# untitled.net
KiCad netlist of a schematic drawn in EAGLE
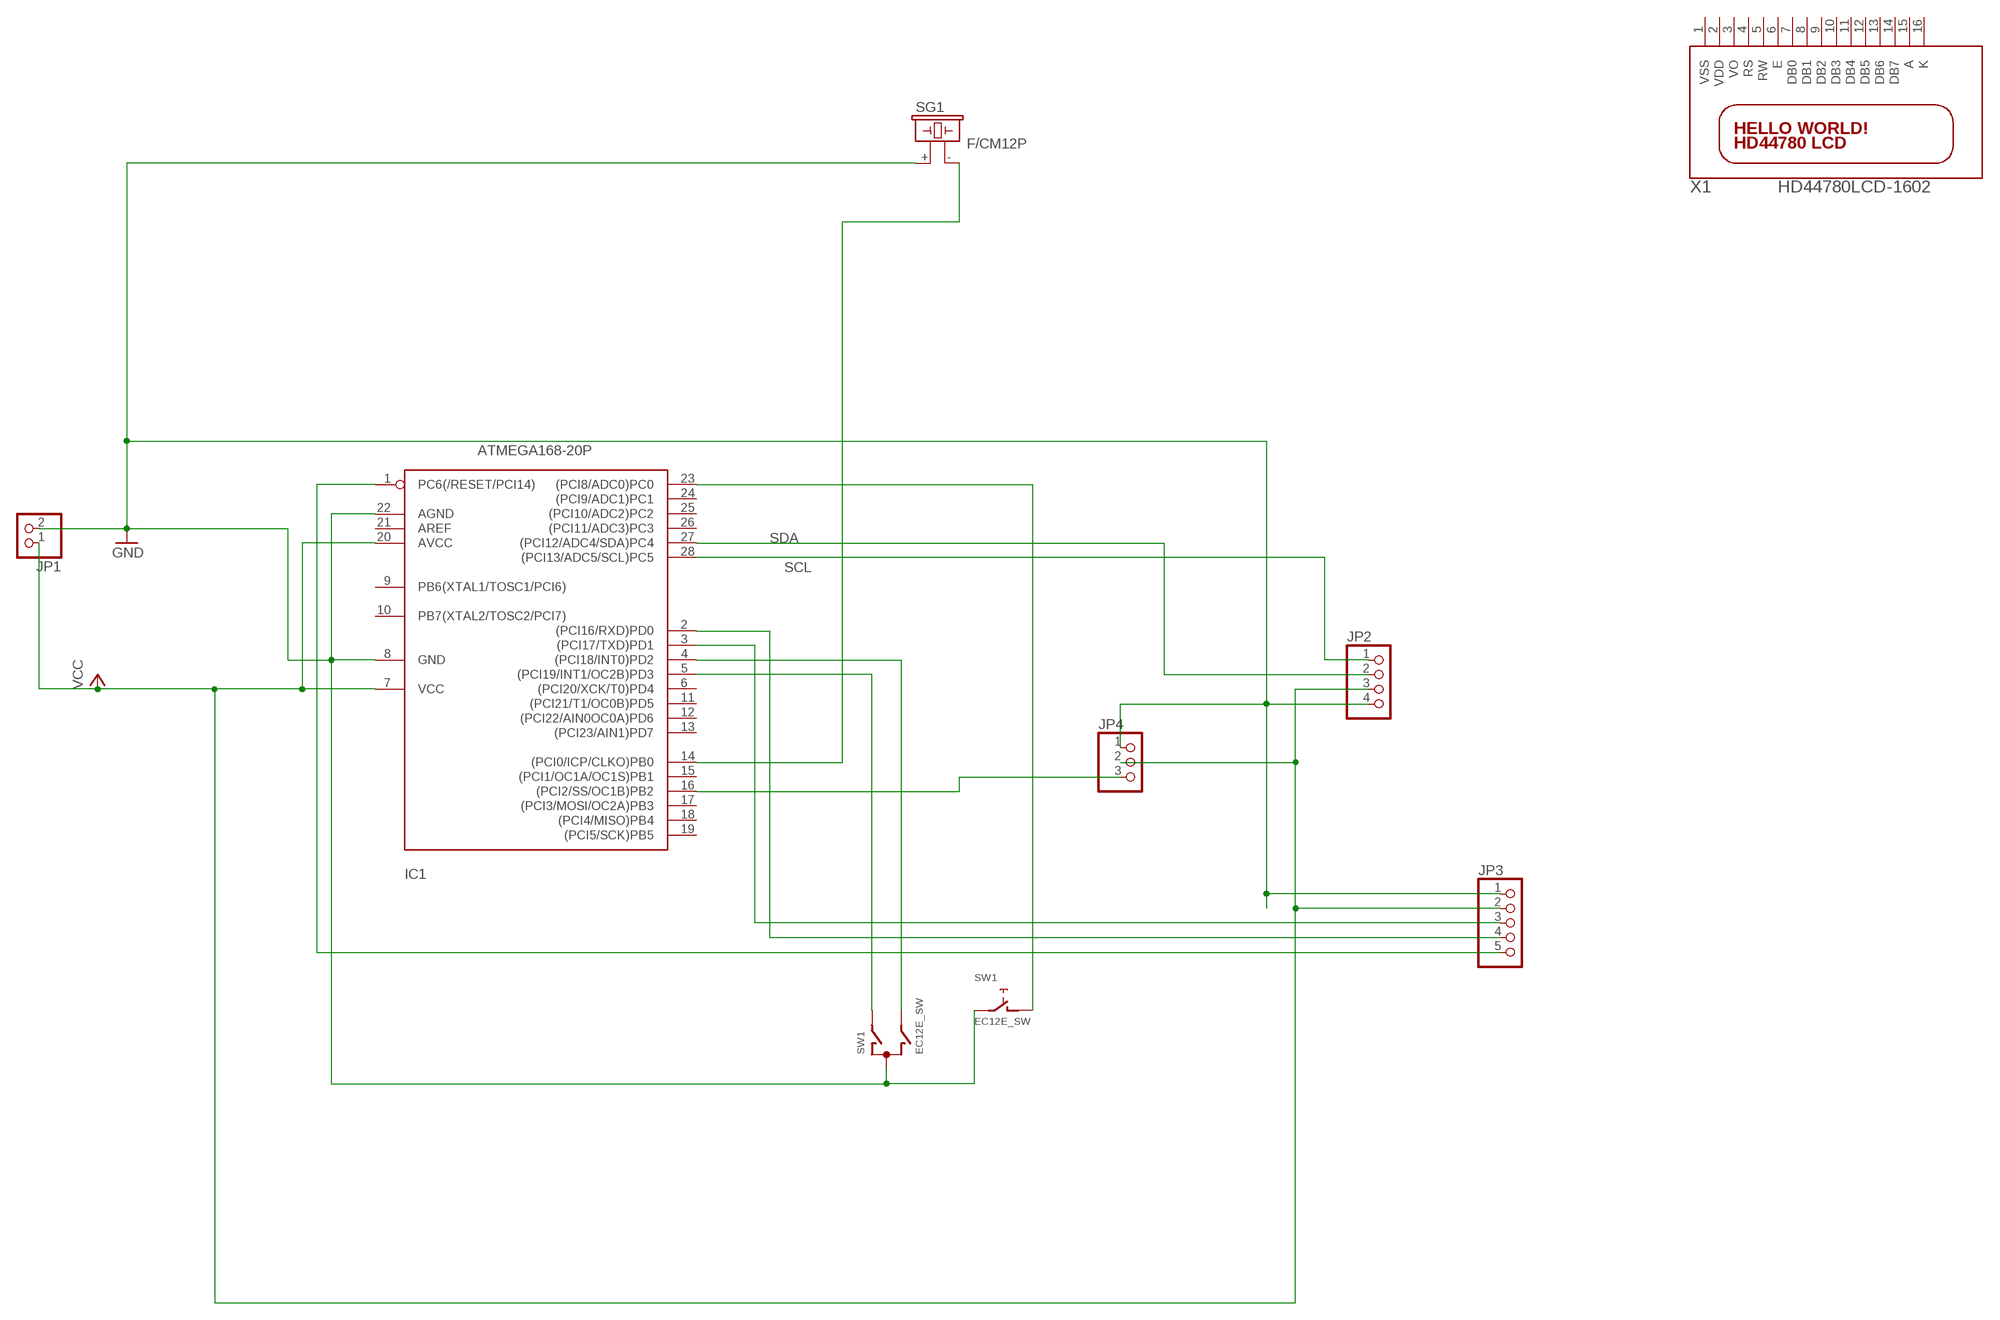
[diagram p0: schematic, sheet 1]

(export (version "E")
  (design (tool "Eeschema 10.0.6"))
  (components
    (comp (ref "IC1")
      (value "ATMEGA168-20P")
      (footprint "eagle-import:DIL28-3")
      (libsource (lib "eagle-import") (part "ATMEGA168P-20"))
    )
    (comp (ref "JP1")
      (value "PINHD-1X2")
      (footprint "eagle-import:1X02")
      (libsource (lib "eagle-import") (part "PINHD-1X2"))
    )
    (comp (ref "JP2")
      (value "PINHD-1X4")
      (footprint "eagle-import:1X04")
      (libsource (lib "eagle-import") (part "PINHD-1X4"))
    )
    (comp (ref "JP3")
      (value "PINHD-1X5")
      (footprint "eagle-import:1X05")
      (libsource (lib "eagle-import") (part "PINHD-1X5"))
    )
    (comp (ref "JP4")
      (value "PINHD-1X3")
      (footprint "eagle-import:1X03")
      (libsource (lib "eagle-import") (part "PINHD-1X3"))
    )
    (comp (ref "SG1")
      (value "F/CM12P")
      (footprint "eagle-import:F_CM12P")
      (libsource (lib "eagle-import") (part "F/CM12P"))
    )
    (comp (ref "SW1")
      (value "EC12E_SW")
      (footprint "eagle-import:ALPS_EC12E_SW")
      (fields (field (name "MPN") "EC12E2424407"))
      (libsource (lib "eagle-import") (part "EC12E_SW"))
    )
    (comp (ref "X1")
      (value "HD44780LCD-1602")
      (footprint "eagle-import:LCD1602")
      (libsource (lib "eagle-import") (part "HD44780LCD-1602"))
    )
  )
  (nets
    (net (code "1") (name "/SCL") (class "Default")
      (node (ref "IC1") (pin "28") (pinfunction "(PCI13/ADC5/SCL)PC5_28") (pintype "bidirectional"))
      (node (ref "JP2") (pin "1") (pinfunction "1_1") (pintype "passive"))
    )
    (net (code "2") (name "/SDA") (class "Default")
      (node (ref "IC1") (pin "27") (pinfunction "(PCI12/ADC4/SDA)PC4_27") (pintype "bidirectional"))
      (node (ref "JP2") (pin "2") (pinfunction "2_2") (pintype "passive"))
    )
    (net (code "3") (name "/VDD") (class "Default")
      (node (ref "X1") (pin "2") (pinfunction "VDD_2") (pintype "power_in"))
    )
    (net (code "4") (name "/VSS") (class "Default")
      (node (ref "X1") (pin "1") (pinfunction "VSS_1") (pintype "power_in"))
    )
    (net (code "5") (name "GND") (class "Default")
      (node (ref "IC1") (pin "22") (pinfunction "AGND_22") (pintype "bidirectional"))
      (node (ref "IC1") (pin "8") (pinfunction "GND_8") (pintype "bidirectional"))
      (node (ref "JP1") (pin "2") (pinfunction "2_2") (pintype "passive"))
      (node (ref "JP2") (pin "4") (pinfunction "4_4") (pintype "passive"))
      (node (ref "JP3") (pin "1") (pinfunction "1_1") (pintype "passive"))
      (node (ref "JP4") (pin "1") (pinfunction "1_1") (pintype "passive"))
      (node (ref "SG1") (pin "+") (pinfunction "1_+") (pintype "passive"))
      (node (ref "SW1") (pin "C") (pinfunction "C_C") (pintype "passive"))
      (node (ref "SW1") (pin "E") (pinfunction "2_E") (pintype "passive"))
    )
    (net (code "6") (name "Net-(IC1-(PCI0{slash}ICP{slash}CLKO)PB0)") (class "Default")
      (node (ref "IC1") (pin "14") (pinfunction "(PCI0/ICP/CLKO)PB0_14") (pintype "bidirectional"))
      (node (ref "SG1") (pin "-") (pinfunction "2_-") (pintype "passive"))
    )
    (net (code "7") (name "Net-(IC1-(PCI2{slash}SS{slash}OC1B)PB2)") (class "Default")
      (node (ref "IC1") (pin "16") (pinfunction "(PCI2/SS/OC1B)PB2_16") (pintype "bidirectional"))
      (node (ref "JP4") (pin "3") (pinfunction "3_3") (pintype "passive"))
    )
    (net (code "8") (name "Net-(IC1-(PCI8{slash}ADC0)PC0)") (class "Default")
      (node (ref "IC1") (pin "23") (pinfunction "(PCI8/ADC0)PC0_23") (pintype "bidirectional"))
      (node (ref "SW1") (pin "D") (pinfunction "1_D") (pintype "passive"))
    )
    (net (code "9") (name "Net-(IC1-(PCI16{slash}RXD)PD0)") (class "Default")
      (node (ref "IC1") (pin "2") (pinfunction "(PCI16/RXD)PD0_2") (pintype "bidirectional"))
      (node (ref "JP3") (pin "4") (pinfunction "4_4") (pintype "passive"))
    )
    (net (code "10") (name "Net-(IC1-(PCI17{slash}TXD)PD1)") (class "Default")
      (node (ref "IC1") (pin "3") (pinfunction "(PCI17/TXD)PD1_3") (pintype "bidirectional"))
      (node (ref "JP3") (pin "3") (pinfunction "3_3") (pintype "passive"))
    )
    (net (code "11") (name "Net-(IC1-(PCI18{slash}INT0)PD2)") (class "Default")
      (node (ref "IC1") (pin "4") (pinfunction "(PCI18/INT0)PD2_4") (pintype "bidirectional"))
      (node (ref "SW1") (pin "B") (pinfunction "B_B") (pintype "passive"))
    )
    (net (code "12") (name "Net-(IC1-(PCI19{slash}INT1{slash}OC2B)PD3)") (class "Default")
      (node (ref "IC1") (pin "5") (pinfunction "(PCI19/INT1/OC2B)PD3_5") (pintype "bidirectional"))
      (node (ref "SW1") (pin "A") (pinfunction "A_A") (pintype "passive"))
    )
    (net (code "13") (name "Net-(IC1-PC6({slash}RESET{slash}PCI14))") (class "Default")
      (node (ref "IC1") (pin "1") (pinfunction "PC6(/RESET/PCI14)_1") (pintype "bidirectional"))
      (node (ref "JP3") (pin "5") (pinfunction "5_5") (pintype "passive"))
    )
    (net (code "14") (name "VCC") (class "Default")
      (node (ref "IC1") (pin "20") (pinfunction "AVCC_20") (pintype "bidirectional"))
      (node (ref "IC1") (pin "7") (pinfunction "VCC_7") (pintype "bidirectional"))
      (node (ref "JP1") (pin "1") (pinfunction "1_1") (pintype "passive"))
      (node (ref "JP2") (pin "3") (pinfunction "3_3") (pintype "passive"))
      (node (ref "JP3") (pin "2") (pinfunction "2_2") (pintype "passive"))
      (node (ref "JP4") (pin "2") (pinfunction "2_2") (pintype "passive"))
    )
    (net (code "15") (name "unconnected-(IC1-(PCI1{slash}OC1A{slash}OC1S)PB1-Pad15)") (class "Default")
      (node (ref "IC1") (pin "15") (pinfunction "(PCI1/OC1A/OC1S)PB1_15") (pintype "bidirectional"))
    )
    (net (code "16") (name "unconnected-(IC1-(PCI3{slash}MOSI{slash}OC2A)PB3-Pad17)") (class "Default")
      (node (ref "IC1") (pin "17") (pinfunction "(PCI3/MOSI/OC2A)PB3_17") (pintype "bidirectional"))
    )
    (net (code "17") (name "unconnected-(IC1-(PCI4{slash}MISO)PB4-Pad18)") (class "Default")
      (node (ref "IC1") (pin "18") (pinfunction "(PCI4/MISO)PB4_18") (pintype "bidirectional"))
    )
    (net (code "18") (name "unconnected-(IC1-(PCI5{slash}SCK)PB5-Pad19)") (class "Default")
      (node (ref "IC1") (pin "19") (pinfunction "(PCI5/SCK)PB5_19") (pintype "bidirectional"))
    )
    (net (code "19") (name "unconnected-(IC1-(PCI9{slash}ADC1)PC1-Pad24)") (class "Default")
      (node (ref "IC1") (pin "24") (pinfunction "(PCI9/ADC1)PC1_24") (pintype "bidirectional"))
    )
    (net (code "20") (name "unconnected-(IC1-(PCI10{slash}ADC2)PC2-Pad25)") (class "Default")
      (node (ref "IC1") (pin "25") (pinfunction "(PCI10/ADC2)PC2_25") (pintype "bidirectional"))
    )
    (net (code "21") (name "unconnected-(IC1-(PCI11{slash}ADC3)PC3-Pad26)") (class "Default")
      (node (ref "IC1") (pin "26") (pinfunction "(PCI11/ADC3)PC3_26") (pintype "bidirectional"))
    )
    (net (code "22") (name "unconnected-(IC1-(PCI20{slash}XCK{slash}T0)PD4-Pad6)") (class "Default")
      (node (ref "IC1") (pin "6") (pinfunction "(PCI20/XCK/T0)PD4_6") (pintype "bidirectional"))
    )
    (net (code "23") (name "unconnected-(IC1-(PCI21{slash}T1{slash}OC0B)PD5-Pad11)") (class "Default")
      (node (ref "IC1") (pin "11") (pinfunction "(PCI21/T1/OC0B)PD5_11") (pintype "bidirectional"))
    )
    (net (code "24") (name "unconnected-(IC1-(PCI22{slash}AIN0OC0A)PD6-Pad12)") (class "Default")
      (node (ref "IC1") (pin "12") (pinfunction "(PCI22/AIN0OC0A)PD6_12") (pintype "bidirectional"))
    )
    (net (code "25") (name "unconnected-(IC1-(PCI23{slash}AIN1)PD7-Pad13)") (class "Default")
      (node (ref "IC1") (pin "13") (pinfunction "(PCI23/AIN1)PD7_13") (pintype "bidirectional"))
    )
    (net (code "26") (name "unconnected-(IC1-AREF-Pad21)") (class "Default")
      (node (ref "IC1") (pin "21") (pinfunction "AREF_21") (pintype "bidirectional"))
    )
    (net (code "27") (name "unconnected-(IC1-PB6(XTAL1{slash}TOSC1{slash}PCI6)-Pad9)") (class "Default")
      (node (ref "IC1") (pin "9") (pinfunction "PB6(XTAL1/TOSC1/PCI6)_9") (pintype "bidirectional"))
    )
    (net (code "28") (name "unconnected-(IC1-PB7(XTAL2{slash}TOSC2{slash}PCI7)-Pad10)") (class "Default")
      (node (ref "IC1") (pin "10") (pinfunction "PB7(XTAL2/TOSC2/PCI7)_10") (pintype "bidirectional"))
    )
    (net (code "29") (name "unconnected-(X1-A-Pad15)") (class "Default")
      (node (ref "X1") (pin "15") (pinfunction "A_15") (pintype "input"))
    )
    (net (code "30") (name "unconnected-(X1-DB0-Pad7)") (class "Default")
      (node (ref "X1") (pin "7") (pinfunction "DB0_7") (pintype "bidirectional"))
    )
    (net (code "31") (name "unconnected-(X1-DB1-Pad8)") (class "Default")
      (node (ref "X1") (pin "8") (pinfunction "DB1_8") (pintype "bidirectional"))
    )
    (net (code "32") (name "unconnected-(X1-DB2-Pad9)") (class "Default")
      (node (ref "X1") (pin "9") (pinfunction "DB2_9") (pintype "bidirectional"))
    )
    (net (code "33") (name "unconnected-(X1-DB3-Pad10)") (class "Default")
      (node (ref "X1") (pin "10") (pinfunction "DB3_10") (pintype "bidirectional"))
    )
    (net (code "34") (name "unconnected-(X1-DB4-Pad11)") (class "Default")
      (node (ref "X1") (pin "11") (pinfunction "DB4_11") (pintype "bidirectional"))
    )
    (net (code "35") (name "unconnected-(X1-DB5-Pad12)") (class "Default")
      (node (ref "X1") (pin "12") (pinfunction "DB5_12") (pintype "bidirectional"))
    )
    (net (code "36") (name "unconnected-(X1-DB6-Pad13)") (class "Default")
      (node (ref "X1") (pin "13") (pinfunction "DB6_13") (pintype "bidirectional"))
    )
    (net (code "37") (name "unconnected-(X1-DB7-Pad14)") (class "Default")
      (node (ref "X1") (pin "14") (pinfunction "DB7_14") (pintype "bidirectional"))
    )
    (net (code "38") (name "unconnected-(X1-E-Pad6)") (class "Default")
      (node (ref "X1") (pin "6") (pinfunction "E_6") (pintype "input"))
    )
    (net (code "39") (name "unconnected-(X1-K-Pad16)") (class "Default")
      (node (ref "X1") (pin "16") (pinfunction "K_16") (pintype "input"))
    )
    (net (code "40") (name "unconnected-(X1-RS-Pad4)") (class "Default")
      (node (ref "X1") (pin "4") (pinfunction "RS_4") (pintype "input"))
    )
    (net (code "41") (name "unconnected-(X1-RW-Pad5)") (class "Default")
      (node (ref "X1") (pin "5") (pinfunction "RW_5") (pintype "input"))
    )
    (net (code "42") (name "unconnected-(X1-VO-Pad3)") (class "Default")
      (node (ref "X1") (pin "3") (pinfunction "VO_3") (pintype "input"))
    )
  )
)
